# Camera.net
KiCad netlist of a schematic drawn in Altium Designer
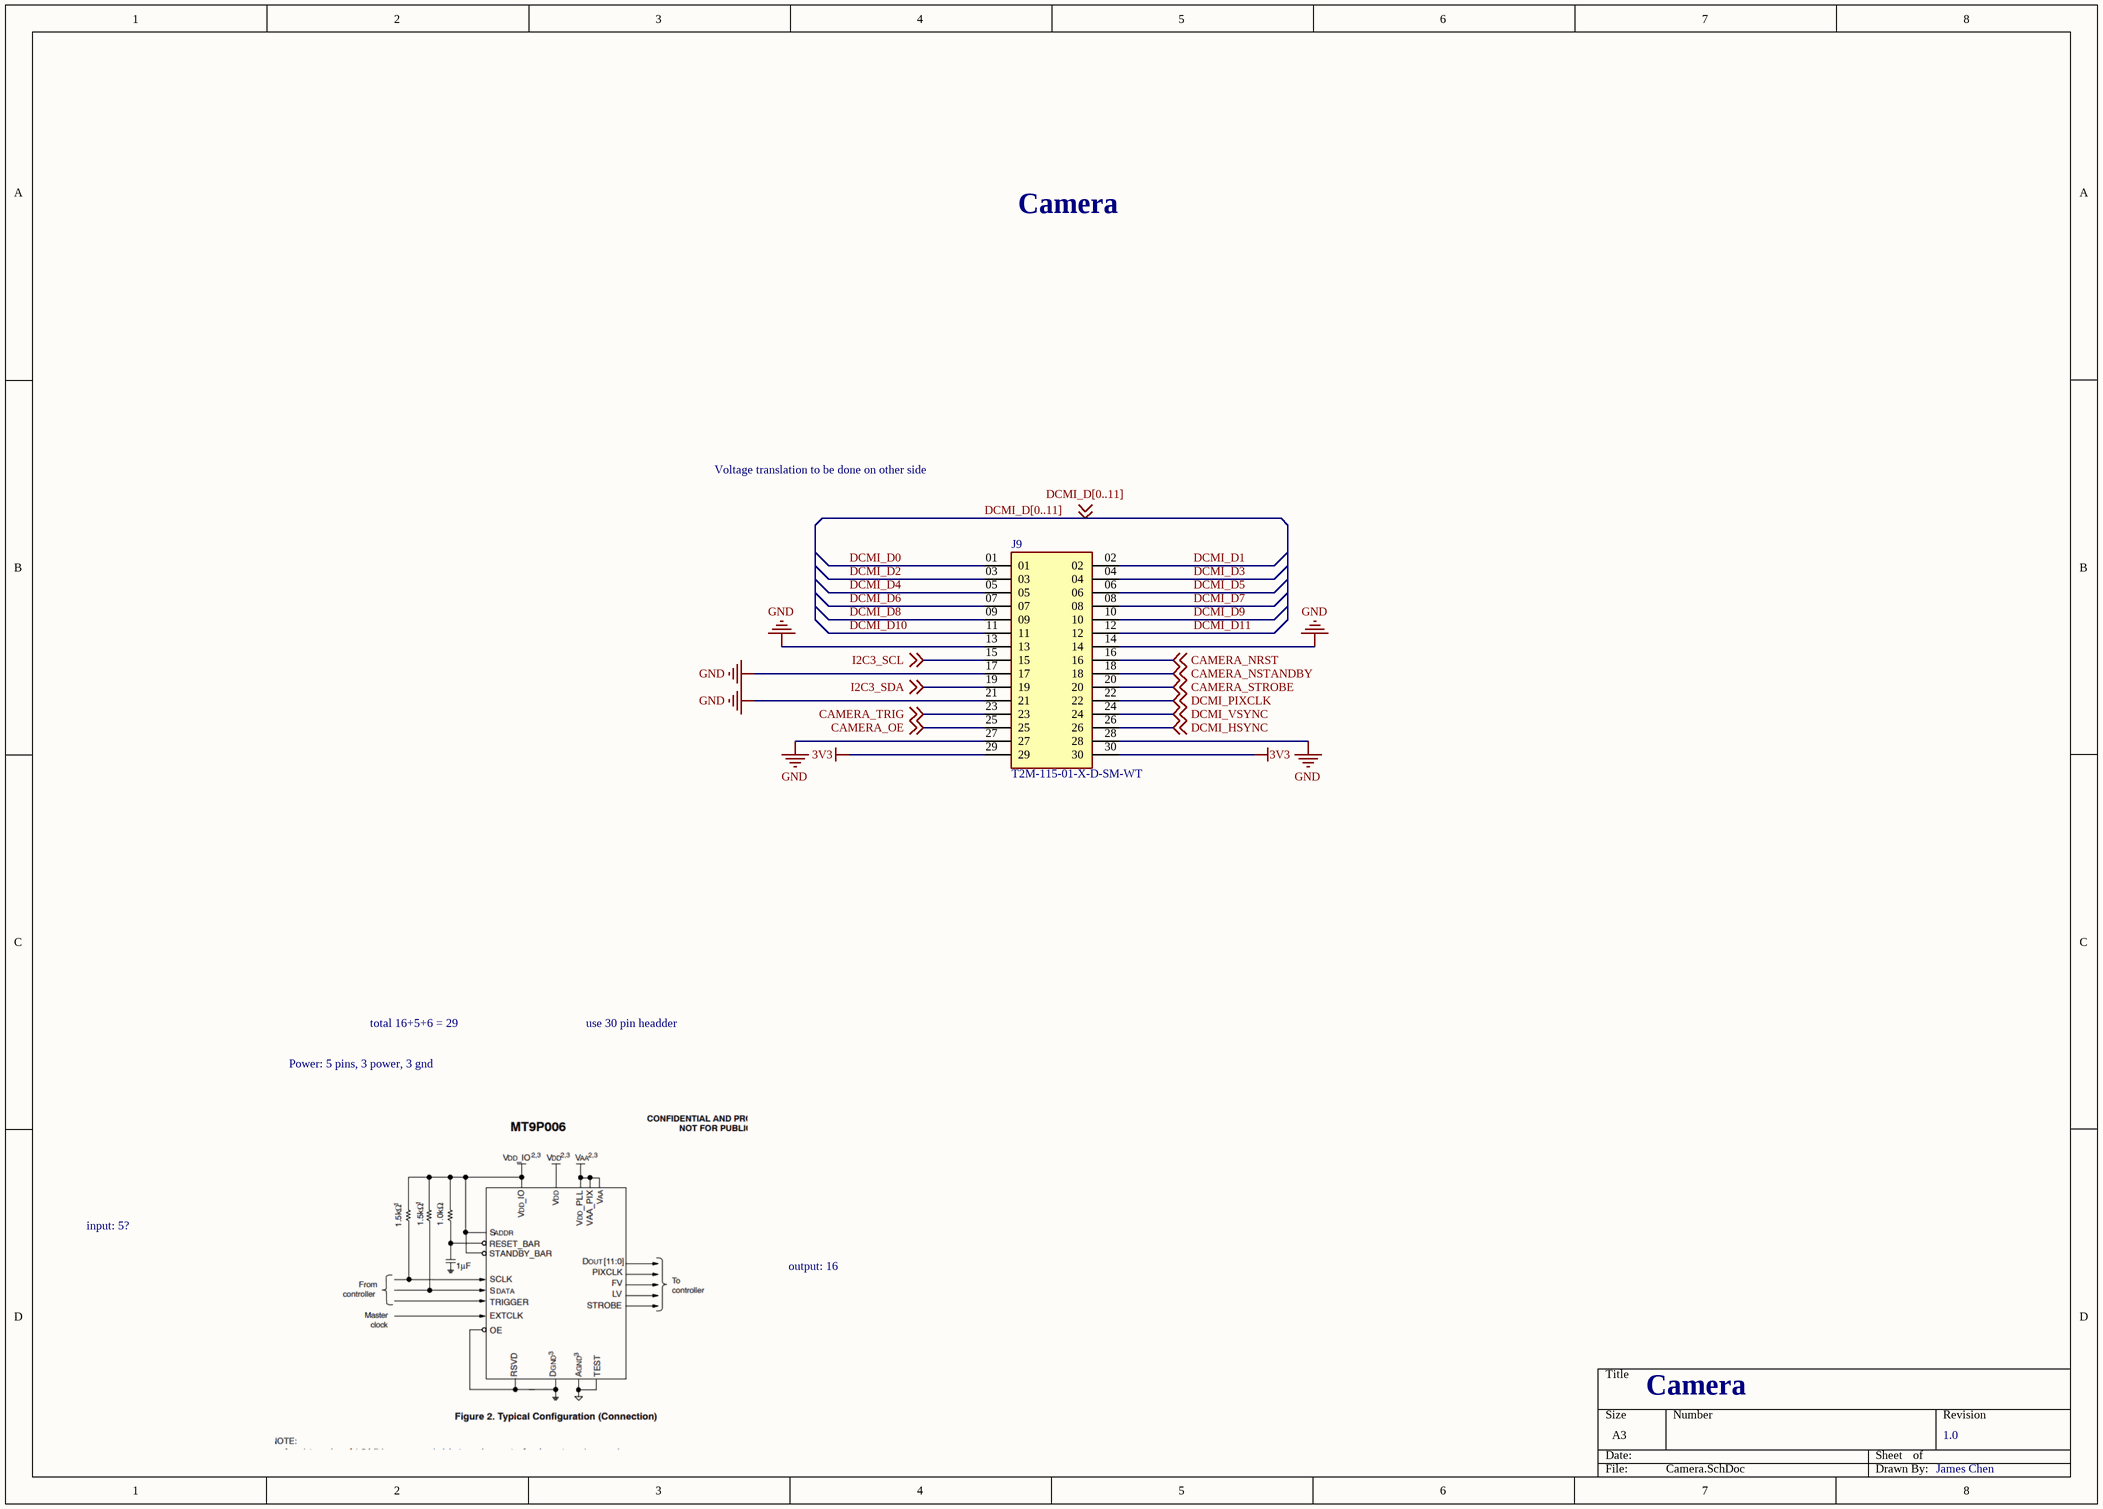
[diagram p0: Camera.SchDoc]

(export (version "E")
  (design (tool "Eeschema 10.0.6"))
  (components
    (comp (ref "J9")
      (value "T2M-115-01-X-D-SM-WT")
      (footprint "T2M-115-01-X-D-SM-WT")
      (description "Headers & Wire Housings High Reliability Tiger Eye Discrete Wire Header, 2.00 mm Pitch")
      (fields (field (name "DISTRIBUTOR PART #") "200-T2M11501LDSMWT"))
      (libsource (lib "OBC Development Board") (part "J-T2M-115-01-X-D-SM-WT"))
    )
  )
  (nets
    (net (code "1") (name "3V3") (class "Default")
      (node (ref "J9") (pin "29") (pinfunction "29_29") (pintype "passive"))
      (node (ref "J9") (pin "30") (pinfunction "30_30") (pintype "passive"))
    )
    (net (code "2") (name "CAMERA_NRST") (class "Default")
      (node (ref "J9") (pin "16") (pinfunction "16_16") (pintype "passive"))
    )
    (net (code "3") (name "CAMERA_NSTANDBY") (class "Default")
      (node (ref "J9") (pin "18") (pinfunction "18_18") (pintype "passive"))
    )
    (net (code "4") (name "CAMERA_OE") (class "Default")
      (node (ref "J9") (pin "25") (pinfunction "25_25") (pintype "passive"))
    )
    (net (code "5") (name "CAMERA_STROBE") (class "Default")
      (node (ref "J9") (pin "20") (pinfunction "20_20") (pintype "passive"))
    )
    (net (code "6") (name "CAMERA_TRIG") (class "Default")
      (node (ref "J9") (pin "23") (pinfunction "23_23") (pintype "passive"))
    )
    (net (code "7") (name "DCMI_D0") (class "Default")
      (node (ref "J9") (pin "01") (pinfunction "01_01") (pintype "passive"))
    )
    (net (code "8") (name "DCMI_D1") (class "Default")
      (node (ref "J9") (pin "02") (pinfunction "02_02") (pintype "passive"))
    )
    (net (code "9") (name "DCMI_D2") (class "Default")
      (node (ref "J9") (pin "03") (pinfunction "03_03") (pintype "passive"))
    )
    (net (code "10") (name "DCMI_D3") (class "Default")
      (node (ref "J9") (pin "04") (pinfunction "04_04") (pintype "passive"))
    )
    (net (code "11") (name "DCMI_D4") (class "Default")
      (node (ref "J9") (pin "05") (pinfunction "05_05") (pintype "passive"))
    )
    (net (code "12") (name "DCMI_D5") (class "Default")
      (node (ref "J9") (pin "06") (pinfunction "06_06") (pintype "passive"))
    )
    (net (code "13") (name "DCMI_D6") (class "Default")
      (node (ref "J9") (pin "07") (pinfunction "07_07") (pintype "passive"))
    )
    (net (code "14") (name "DCMI_D7") (class "Default")
      (node (ref "J9") (pin "08") (pinfunction "08_08") (pintype "passive"))
    )
    (net (code "15") (name "DCMI_D8") (class "Default")
      (node (ref "J9") (pin "09") (pinfunction "09_09") (pintype "passive"))
    )
    (net (code "16") (name "DCMI_D9") (class "Default")
      (node (ref "J9") (pin "10") (pinfunction "10_10") (pintype "passive"))
    )
    (net (code "17") (name "DCMI_D10") (class "Default")
      (node (ref "J9") (pin "11") (pinfunction "11_11") (pintype "passive"))
    )
    (net (code "18") (name "DCMI_D11") (class "Default")
      (node (ref "J9") (pin "12") (pinfunction "12_12") (pintype "passive"))
    )
    (net (code "20") (name "DCMI_HSYNC") (class "Default")
      (node (ref "J9") (pin "26") (pinfunction "26_26") (pintype "passive"))
    )
    (net (code "21") (name "DCMI_PIXCLK") (class "Default")
      (node (ref "J9") (pin "22") (pinfunction "22_22") (pintype "passive"))
    )
    (net (code "22") (name "DCMI_VSYNC") (class "Default")
      (node (ref "J9") (pin "24") (pinfunction "24_24") (pintype "passive"))
    )
    (net (code "23") (name "GND") (class "Default")
      (node (ref "J9") (pin "13") (pinfunction "13_13") (pintype "passive"))
      (node (ref "J9") (pin "14") (pinfunction "14_14") (pintype "passive"))
      (node (ref "J9") (pin "17") (pinfunction "17_17") (pintype "passive"))
      (node (ref "J9") (pin "21") (pinfunction "21_21") (pintype "passive"))
      (node (ref "J9") (pin "27") (pinfunction "27_27") (pintype "passive"))
      (node (ref "J9") (pin "28") (pinfunction "28_28") (pintype "passive"))
    )
    (net (code "24") (name "I2C3_SCL") (class "Default")
      (node (ref "J9") (pin "15") (pinfunction "15_15") (pintype "passive"))
    )
    (net (code "25") (name "I2C3_SDA") (class "Default")
      (node (ref "J9") (pin "19") (pinfunction "19_19") (pintype "passive"))
    )
  )
)
